# working.net
KiCad netlist of a schematic drawn in EAGLE
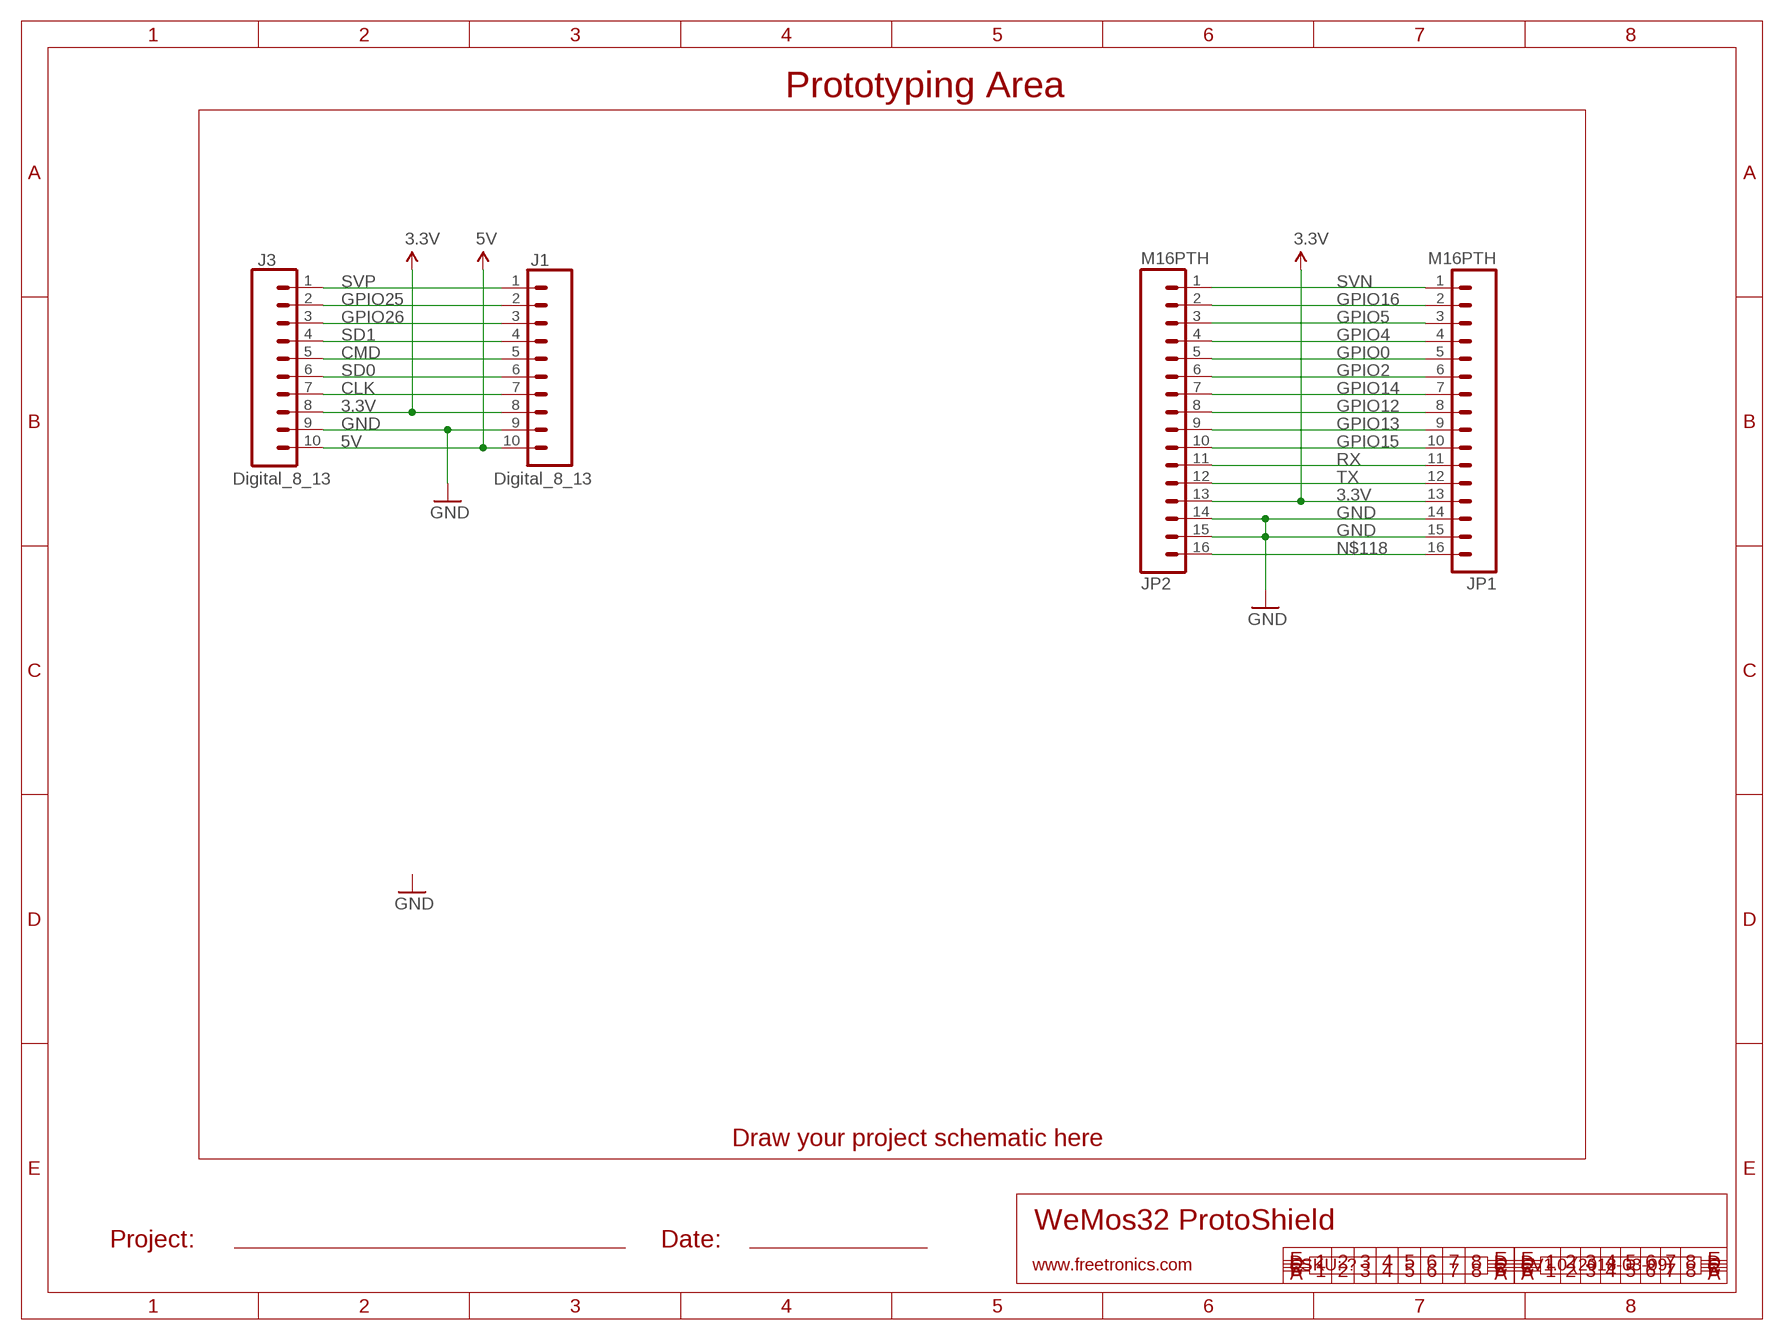
[diagram p0: schematic, sheet 1]

(export (version "E")
  (design (tool "Eeschema 10.0.6"))
  (components
    (comp (ref "J1")
      (value "Digital_8_13")
      (footprint "eagle-import:1X10")
      (libsource (lib "eagle-import") (part "M100.1"))
    )
    (comp (ref "J3")
      (value "Digital_8_13")
      (footprint "eagle-import:1X10")
      (libsource (lib "eagle-import") (part "M100.1"))
    )
    (comp (ref "JP1")
      (value "M16PTH")
      (footprint "eagle-import:1X16")
      (libsource (lib "eagle-import") (part "M16PTH"))
    )
    (comp (ref "JP2")
      (value "M16PTH")
      (footprint "eagle-import:1X16")
      (libsource (lib "eagle-import") (part "M16PTH"))
    )
  )
  (nets
    (net (code "1") (name "/CLK") (class "Default")
      (node (ref "J1") (pin "7") (pinfunction "7_7") (pintype "passive"))
      (node (ref "J3") (pin "7") (pinfunction "7_7") (pintype "passive"))
    )
    (net (code "2") (name "/CMD") (class "Default")
      (node (ref "J1") (pin "5") (pinfunction "5_5") (pintype "passive"))
      (node (ref "J3") (pin "5") (pinfunction "5_5") (pintype "passive"))
    )
    (net (code "3") (name "/GPIO0") (class "Default")
      (node (ref "JP1") (pin "5") (pinfunction "5_5") (pintype "passive"))
      (node (ref "JP2") (pin "5") (pinfunction "5_5") (pintype "passive"))
    )
    (net (code "4") (name "/GPIO2") (class "Default")
      (node (ref "JP1") (pin "6") (pinfunction "6_6") (pintype "passive"))
      (node (ref "JP2") (pin "6") (pinfunction "6_6") (pintype "passive"))
    )
    (net (code "5") (name "/GPIO4") (class "Default")
      (node (ref "JP1") (pin "4") (pinfunction "4_4") (pintype "passive"))
      (node (ref "JP2") (pin "4") (pinfunction "4_4") (pintype "passive"))
    )
    (net (code "6") (name "/GPIO5") (class "Default")
      (node (ref "JP1") (pin "3") (pinfunction "3_3") (pintype "passive"))
      (node (ref "JP2") (pin "3") (pinfunction "3_3") (pintype "passive"))
    )
    (net (code "7") (name "/GPIO12") (class "Default")
      (node (ref "JP1") (pin "8") (pinfunction "8_8") (pintype "passive"))
      (node (ref "JP2") (pin "8") (pinfunction "8_8") (pintype "passive"))
    )
    (net (code "8") (name "/GPIO13") (class "Default")
      (node (ref "JP1") (pin "9") (pinfunction "9_9") (pintype "passive"))
      (node (ref "JP2") (pin "9") (pinfunction "9_9") (pintype "passive"))
    )
    (net (code "9") (name "/GPIO14") (class "Default")
      (node (ref "JP1") (pin "7") (pinfunction "7_7") (pintype "passive"))
      (node (ref "JP2") (pin "7") (pinfunction "7_7") (pintype "passive"))
    )
    (net (code "10") (name "/GPIO15") (class "Default")
      (node (ref "JP1") (pin "10") (pinfunction "10_10") (pintype "passive"))
      (node (ref "JP2") (pin "10") (pinfunction "10_10") (pintype "passive"))
    )
    (net (code "11") (name "/GPIO16") (class "Default")
      (node (ref "JP1") (pin "2") (pinfunction "2_2") (pintype "passive"))
      (node (ref "JP2") (pin "2") (pinfunction "2_2") (pintype "passive"))
    )
    (net (code "12") (name "/GPIO25") (class "Default")
      (node (ref "J1") (pin "2") (pinfunction "2_2") (pintype "passive"))
      (node (ref "J3") (pin "2") (pinfunction "2_2") (pintype "passive"))
    )
    (net (code "13") (name "/GPIO26") (class "Default")
      (node (ref "J1") (pin "3") (pinfunction "3_3") (pintype "passive"))
      (node (ref "J3") (pin "3") (pinfunction "3_3") (pintype "passive"))
    )
    (net (code "14") (name "/N$118") (class "Default")
      (node (ref "JP1") (pin "16") (pinfunction "16_16") (pintype "passive"))
      (node (ref "JP2") (pin "16") (pinfunction "16_16") (pintype "passive"))
    )
    (net (code "15") (name "/RX") (class "Default")
      (node (ref "JP1") (pin "11") (pinfunction "11_11") (pintype "passive"))
      (node (ref "JP2") (pin "11") (pinfunction "11_11") (pintype "passive"))
    )
    (net (code "16") (name "/SD0") (class "Default")
      (node (ref "J1") (pin "6") (pinfunction "6_6") (pintype "passive"))
      (node (ref "J3") (pin "6") (pinfunction "6_6") (pintype "passive"))
    )
    (net (code "17") (name "/SD1") (class "Default")
      (node (ref "J1") (pin "4") (pinfunction "4_4") (pintype "passive"))
      (node (ref "J3") (pin "4") (pinfunction "4_4") (pintype "passive"))
    )
    (net (code "18") (name "/SVN") (class "Default")
      (node (ref "JP1") (pin "1") (pinfunction "1_1") (pintype "passive"))
      (node (ref "JP2") (pin "1") (pinfunction "1_1") (pintype "passive"))
    )
    (net (code "19") (name "/SVP") (class "Default")
      (node (ref "J1") (pin "1") (pinfunction "1_1") (pintype "passive"))
      (node (ref "J3") (pin "1") (pinfunction "1_1") (pintype "passive"))
    )
    (net (code "20") (name "/TX") (class "Default")
      (node (ref "JP1") (pin "12") (pinfunction "12_12") (pintype "passive"))
      (node (ref "JP2") (pin "12") (pinfunction "12_12") (pintype "passive"))
    )
    (net (code "21") (name "3.3V") (class "Default")
      (node (ref "J1") (pin "8") (pinfunction "8_8") (pintype "passive"))
      (node (ref "J3") (pin "8") (pinfunction "8_8") (pintype "passive"))
      (node (ref "JP1") (pin "13") (pinfunction "13_13") (pintype "passive"))
      (node (ref "JP2") (pin "13") (pinfunction "13_13") (pintype "passive"))
    )
    (net (code "22") (name "5V") (class "Default")
      (node (ref "J1") (pin "10") (pinfunction "10_10") (pintype "passive"))
      (node (ref "J3") (pin "10") (pinfunction "10_10") (pintype "passive"))
    )
    (net (code "23") (name "GND") (class "Default")
      (node (ref "J1") (pin "9") (pinfunction "9_9") (pintype "passive"))
      (node (ref "J3") (pin "9") (pinfunction "9_9") (pintype "passive"))
      (node (ref "JP1") (pin "14") (pinfunction "14_14") (pintype "passive"))
      (node (ref "JP1") (pin "15") (pinfunction "15_15") (pintype "passive"))
      (node (ref "JP2") (pin "14") (pinfunction "14_14") (pintype "passive"))
      (node (ref "JP2") (pin "15") (pinfunction "15_15") (pintype "passive"))
    )
  )
)
